# 1-Main.net
KiCad netlist of a schematic drawn in Altium Designer
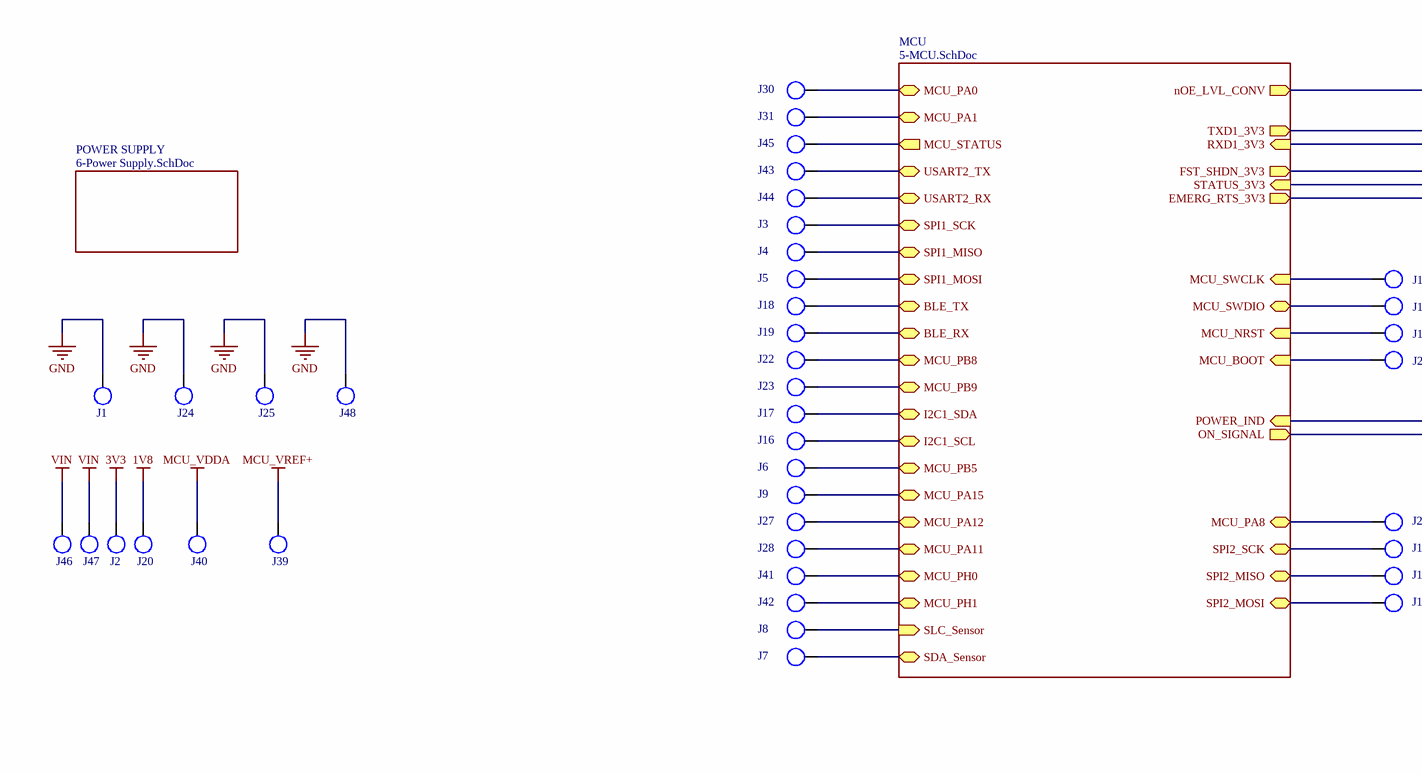
[diagram p0: 1-Main.SchDoc, left]
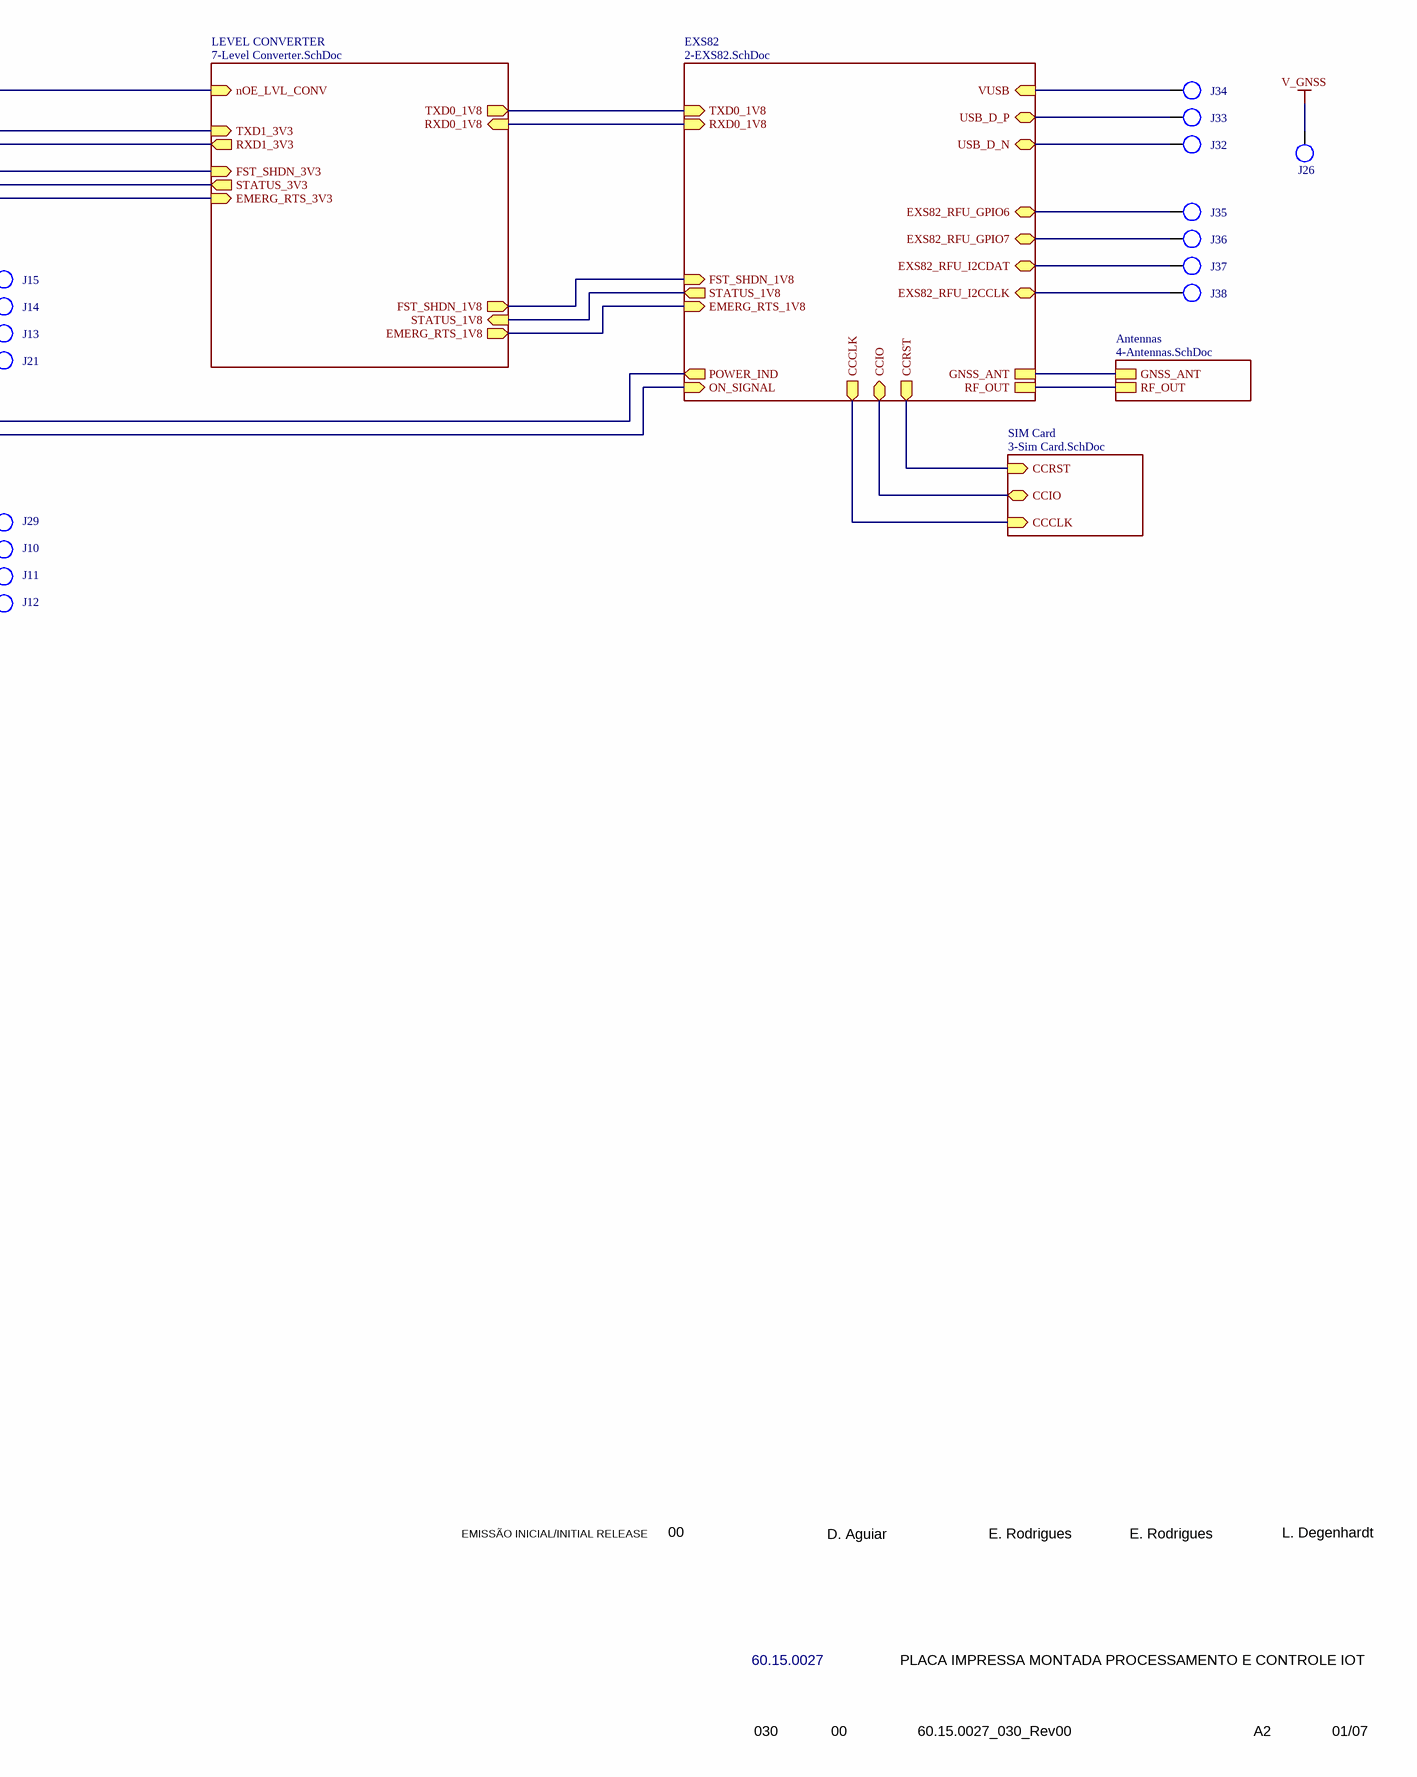
[diagram p1: 1-Main.SchDoc, right]

(export (version "E")
  (design (tool "Eeschema 10.0.6"))
  (components
    (comp (ref "J1")
      (value "CASTELATION")
      (footprint "CASTELATION")
      (libsource (lib "OMNI-SEM-COD") (part "CASTELATION"))
    )
    (comp (ref "J2")
      (value "CASTELATION")
      (footprint "CASTELATION")
      (libsource (lib "OMNI-SEM-COD") (part "CASTELATION"))
    )
    (comp (ref "J3")
      (value "CASTELATION")
      (footprint "CASTELATION")
      (libsource (lib "OMNI-SEM-COD") (part "CASTELATION"))
    )
    (comp (ref "J4")
      (value "CASTELATION")
      (footprint "CASTELATION")
      (libsource (lib "OMNI-SEM-COD") (part "CASTELATION"))
    )
    (comp (ref "J5")
      (value "CASTELATION")
      (footprint "CASTELATION")
      (libsource (lib "OMNI-SEM-COD") (part "CASTELATION"))
    )
    (comp (ref "J6")
      (value "CASTELATION")
      (footprint "CASTELATION")
      (libsource (lib "OMNI-SEM-COD") (part "CASTELATION"))
    )
    (comp (ref "J7")
      (value "CASTELATION")
      (footprint "CASTELATION")
      (libsource (lib "OMNI-SEM-COD") (part "CASTELATION"))
    )
    (comp (ref "J8")
      (value "CASTELATION")
      (footprint "CASTELATION")
      (libsource (lib "OMNI-SEM-COD") (part "CASTELATION"))
    )
    (comp (ref "J9")
      (value "CASTELATION")
      (footprint "CASTELATION")
      (libsource (lib "OMNI-SEM-COD") (part "CASTELATION"))
    )
    (comp (ref "J10")
      (value "CASTELATION")
      (footprint "CASTELATION")
      (libsource (lib "OMNI-SEM-COD") (part "CASTELATION"))
    )
    (comp (ref "J11")
      (value "CASTELATION")
      (footprint "CASTELATION")
      (libsource (lib "OMNI-SEM-COD") (part "CASTELATION"))
    )
    (comp (ref "J12")
      (value "CASTELATION")
      (footprint "CASTELATION")
      (libsource (lib "OMNI-SEM-COD") (part "CASTELATION"))
    )
    (comp (ref "J13")
      (value "CASTELATION")
      (footprint "CASTELATION")
      (libsource (lib "OMNI-SEM-COD") (part "CASTELATION"))
    )
    (comp (ref "J14")
      (value "CASTELATION")
      (footprint "CASTELATION")
      (libsource (lib "OMNI-SEM-COD") (part "CASTELATION"))
    )
    (comp (ref "J15")
      (value "CASTELATION")
      (footprint "CASTELATION")
      (libsource (lib "OMNI-SEM-COD") (part "CASTELATION"))
    )
    (comp (ref "J16")
      (value "CASTELATION")
      (footprint "CASTELATION")
      (libsource (lib "OMNI-SEM-COD") (part "CASTELATION"))
    )
    (comp (ref "J17")
      (value "CASTELATION")
      (footprint "CASTELATION")
      (libsource (lib "OMNI-SEM-COD") (part "CASTELATION"))
    )
    (comp (ref "J18")
      (value "CASTELATION")
      (footprint "CASTELATION")
      (libsource (lib "OMNI-SEM-COD") (part "CASTELATION"))
    )
    (comp (ref "J19")
      (value "CASTELATION")
      (footprint "CASTELATION")
      (libsource (lib "OMNI-SEM-COD") (part "CASTELATION"))
    )
    (comp (ref "J20")
      (value "CASTELATION")
      (footprint "CASTELATION")
      (libsource (lib "OMNI-SEM-COD") (part "CASTELATION"))
    )
    (comp (ref "J21")
      (value "CASTELATION")
      (footprint "CASTELATION")
      (libsource (lib "OMNI-SEM-COD") (part "CASTELATION"))
    )
    (comp (ref "J22")
      (value "CASTELATION")
      (footprint "CASTELATION")
      (libsource (lib "OMNI-SEM-COD") (part "CASTELATION"))
    )
    (comp (ref "J23")
      (value "CASTELATION")
      (footprint "CASTELATION")
      (libsource (lib "OMNI-SEM-COD") (part "CASTELATION"))
    )
    (comp (ref "J24")
      (value "CASTELATION")
      (footprint "CASTELATION")
      (libsource (lib "OMNI-SEM-COD") (part "CASTELATION"))
    )
    (comp (ref "J25")
      (value "CASTELATION")
      (footprint "CASTELATION")
      (libsource (lib "OMNI-SEM-COD") (part "CASTELATION"))
    )
    (comp (ref "J26")
      (value "CASTELATION")
      (footprint "CASTELATION")
      (libsource (lib "OMNI-SEM-COD") (part "CASTELATION"))
    )
    (comp (ref "J27")
      (value "CASTELATION")
      (footprint "CASTELATION")
      (libsource (lib "OMNI-SEM-COD") (part "CASTELATION"))
    )
    (comp (ref "J28")
      (value "CASTELATION")
      (footprint "CASTELATION")
      (libsource (lib "OMNI-SEM-COD") (part "CASTELATION"))
    )
    (comp (ref "J29")
      (value "CASTELATION")
      (footprint "CASTELATION")
      (libsource (lib "OMNI-SEM-COD") (part "CASTELATION"))
    )
    (comp (ref "J30")
      (value "CASTELATION")
      (footprint "CASTELATION")
      (libsource (lib "OMNI-SEM-COD") (part "CASTELATION"))
    )
    (comp (ref "J31")
      (value "CASTELATION")
      (footprint "CASTELATION")
      (libsource (lib "OMNI-SEM-COD") (part "CASTELATION"))
    )
    (comp (ref "J32")
      (value "CASTELATION")
      (footprint "CASTELATION")
      (libsource (lib "OMNI-SEM-COD") (part "CASTELATION"))
    )
    (comp (ref "J33")
      (value "CASTELATION")
      (footprint "CASTELATION")
      (libsource (lib "OMNI-SEM-COD") (part "CASTELATION"))
    )
    (comp (ref "J34")
      (value "CASTELATION")
      (footprint "CASTELATION")
      (libsource (lib "OMNI-SEM-COD") (part "CASTELATION"))
    )
    (comp (ref "J35")
      (value "CASTELATION")
      (footprint "CASTELATION")
      (libsource (lib "OMNI-SEM-COD") (part "CASTELATION"))
    )
    (comp (ref "J36")
      (value "CASTELATION")
      (footprint "CASTELATION")
      (libsource (lib "OMNI-SEM-COD") (part "CASTELATION"))
    )
    (comp (ref "J37")
      (value "CASTELATION")
      (footprint "CASTELATION")
      (libsource (lib "OMNI-SEM-COD") (part "CASTELATION"))
    )
    (comp (ref "J38")
      (value "CASTELATION")
      (footprint "CASTELATION")
      (libsource (lib "OMNI-SEM-COD") (part "CASTELATION"))
    )
    (comp (ref "J39")
      (value "CASTELATION")
      (footprint "CASTELATION")
      (libsource (lib "OMNI-SEM-COD") (part "CASTELATION"))
    )
    (comp (ref "J40")
      (value "CASTELATION")
      (footprint "CASTELATION")
      (libsource (lib "OMNI-SEM-COD") (part "CASTELATION"))
    )
    (comp (ref "J41")
      (value "CASTELATION")
      (footprint "CASTELATION")
      (libsource (lib "OMNI-SEM-COD") (part "CASTELATION"))
    )
    (comp (ref "J42")
      (value "CASTELATION")
      (footprint "CASTELATION")
      (libsource (lib "OMNI-SEM-COD") (part "CASTELATION"))
    )
    (comp (ref "J43")
      (value "CASTELATION")
      (footprint "CASTELATION")
      (libsource (lib "OMNI-SEM-COD") (part "CASTELATION"))
    )
    (comp (ref "J44")
      (value "CASTELATION")
      (footprint "CASTELATION")
      (libsource (lib "OMNI-SEM-COD") (part "CASTELATION"))
    )
    (comp (ref "J45")
      (value "CASTELATION")
      (footprint "CASTELATION")
      (libsource (lib "OMNI-SEM-COD") (part "CASTELATION"))
    )
    (comp (ref "J46")
      (value "CASTELATION")
      (footprint "CASTELATION")
      (libsource (lib "OMNI-SEM-COD") (part "CASTELATION"))
    )
    (comp (ref "J47")
      (value "CASTELATION")
      (footprint "CASTELATION")
      (libsource (lib "OMNI-SEM-COD") (part "CASTELATION"))
    )
    (comp (ref "J48")
      (value "CASTELATION")
      (footprint "CASTELATION")
      (libsource (lib "OMNI-SEM-COD") (part "CASTELATION"))
    )
  )
  (nets
    (net (code "1") (name "/BLE_RX") (class "Default")
      (node (ref "J19") (pin "1") (pinfunction "1_1") (pintype "passive"))
    )
    (net (code "2") (name "/BLE_TX") (class "Default")
      (node (ref "J18") (pin "1") (pinfunction "1_1") (pintype "passive"))
    )
    (net (code "8") (name "/EXS82_RFU_GPIO6") (class "Default")
      (node (ref "J35") (pin "1") (pinfunction "1_1") (pintype "passive"))
    )
    (net (code "9") (name "/EXS82_RFU_GPIO7") (class "Default")
      (node (ref "J36") (pin "1") (pinfunction "1_1") (pintype "passive"))
    )
    (net (code "10") (name "/EXS82_RFU_I2CCLK") (class "Default")
      (node (ref "J38") (pin "1") (pinfunction "1_1") (pintype "passive"))
    )
    (net (code "11") (name "/EXS82_RFU_I2CDAT") (class "Default")
      (node (ref "J37") (pin "1") (pinfunction "1_1") (pintype "passive"))
    )
    (net (code "15") (name "/I2C1_SCL") (class "Default")
      (node (ref "J16") (pin "1") (pinfunction "1_1") (pintype "passive"))
    )
    (net (code "16") (name "/I2C1_SDA") (class "Default")
      (node (ref "J17") (pin "1") (pinfunction "1_1") (pintype "passive"))
    )
    (net (code "17") (name "/MCU_BOOT") (class "Default")
      (node (ref "J21") (pin "1") (pinfunction "1_1") (pintype "passive"))
    )
    (net (code "18") (name "/MCU_NRST") (class "Default")
      (node (ref "J13") (pin "1") (pinfunction "1_1") (pintype "passive"))
    )
    (net (code "19") (name "/MCU_PA0") (class "Default")
      (node (ref "J30") (pin "1") (pinfunction "1_1") (pintype "passive"))
    )
    (net (code "20") (name "/MCU_PA1") (class "Default")
      (node (ref "J31") (pin "1") (pinfunction "1_1") (pintype "passive"))
    )
    (net (code "21") (name "/MCU_PA8") (class "Default")
      (node (ref "J29") (pin "1") (pinfunction "1_1") (pintype "passive"))
    )
    (net (code "22") (name "/MCU_PA11") (class "Default")
      (node (ref "J28") (pin "1") (pinfunction "1_1") (pintype "passive"))
    )
    (net (code "23") (name "/MCU_PA12") (class "Default")
      (node (ref "J27") (pin "1") (pinfunction "1_1") (pintype "passive"))
    )
    (net (code "24") (name "/MCU_PA15") (class "Default")
      (node (ref "J9") (pin "1") (pinfunction "1_1") (pintype "passive"))
    )
    (net (code "25") (name "/MCU_PB5") (class "Default")
      (node (ref "J6") (pin "1") (pinfunction "1_1") (pintype "passive"))
    )
    (net (code "26") (name "/MCU_PB8") (class "Default")
      (node (ref "J22") (pin "1") (pinfunction "1_1") (pintype "passive"))
    )
    (net (code "27") (name "/MCU_PB9") (class "Default")
      (node (ref "J23") (pin "1") (pinfunction "1_1") (pintype "passive"))
    )
    (net (code "28") (name "/MCU_PH0") (class "Default")
      (node (ref "J41") (pin "1") (pinfunction "1_1") (pintype "passive"))
    )
    (net (code "29") (name "/MCU_PH1") (class "Default")
      (node (ref "J42") (pin "1") (pinfunction "1_1") (pintype "passive"))
    )
    (net (code "30") (name "/MCU_STATUS") (class "Default")
      (node (ref "J45") (pin "1") (pinfunction "1_1") (pintype "passive"))
    )
    (net (code "31") (name "/MCU_SWCLK") (class "Default")
      (node (ref "J15") (pin "1") (pinfunction "1_1") (pintype "passive"))
    )
    (net (code "32") (name "/MCU_SWDIO") (class "Default")
      (node (ref "J14") (pin "1") (pinfunction "1_1") (pintype "passive"))
    )
    (net (code "38") (name "/SDA_Sensor") (class "Default")
      (node (ref "J7") (pin "1") (pinfunction "1_1") (pintype "passive"))
    )
    (net (code "39") (name "/SLC_Sensor") (class "Default")
      (node (ref "J8") (pin "1") (pinfunction "1_1") (pintype "passive"))
    )
    (net (code "40") (name "/SPI1_MISO") (class "Default")
      (node (ref "J4") (pin "1") (pinfunction "1_1") (pintype "passive"))
    )
    (net (code "41") (name "/SPI1_MOSI") (class "Default")
      (node (ref "J5") (pin "1") (pinfunction "1_1") (pintype "passive"))
    )
    (net (code "42") (name "/SPI1_SCK") (class "Default")
      (node (ref "J3") (pin "1") (pinfunction "1_1") (pintype "passive"))
    )
    (net (code "43") (name "/SPI2_MISO") (class "Default")
      (node (ref "J11") (pin "1") (pinfunction "1_1") (pintype "passive"))
    )
    (net (code "44") (name "/SPI2_MOSI") (class "Default")
      (node (ref "J12") (pin "1") (pinfunction "1_1") (pintype "passive"))
    )
    (net (code "45") (name "/SPI2_SCK") (class "Default")
      (node (ref "J10") (pin "1") (pinfunction "1_1") (pintype "passive"))
    )
    (net (code "50") (name "/USART2_RX") (class "Default")
      (node (ref "J44") (pin "1") (pinfunction "1_1") (pintype "passive"))
    )
    (net (code "51") (name "/USART2_TX") (class "Default")
      (node (ref "J43") (pin "1") (pinfunction "1_1") (pintype "passive"))
    )
    (net (code "52") (name "/USB_D_N") (class "Default")
      (node (ref "J32") (pin "1") (pinfunction "1_1") (pintype "passive"))
    )
    (net (code "53") (name "/USB_D_P") (class "Default")
      (node (ref "J33") (pin "1") (pinfunction "1_1") (pintype "passive"))
    )
    (net (code "54") (name "/VUSB") (class "Default")
      (node (ref "J34") (pin "1") (pinfunction "1_1") (pintype "passive"))
    )
    (net (code "56") (name "1V8") (class "Default")
      (node (ref "J20") (pin "1") (pinfunction "1_1") (pintype "passive"))
    )
    (net (code "57") (name "3V3") (class "Default")
      (node (ref "J2") (pin "1") (pinfunction "1_1") (pintype "passive"))
    )
    (net (code "58") (name "GND") (class "Default")
      (node (ref "J1") (pin "1") (pinfunction "1_1") (pintype "passive"))
      (node (ref "J24") (pin "1") (pinfunction "1_1") (pintype "passive"))
      (node (ref "J25") (pin "1") (pinfunction "1_1") (pintype "passive"))
      (node (ref "J48") (pin "1") (pinfunction "1_1") (pintype "passive"))
    )
    (net (code "59") (name "MCU_VDDA") (class "Default")
      (node (ref "J40") (pin "1") (pinfunction "1_1") (pintype "passive"))
    )
    (net (code "60") (name "MCU_VREF+") (class "Default")
      (node (ref "J39") (pin "1") (pinfunction "1_1") (pintype "passive"))
    )
    (net (code "61") (name "VIN") (class "Default")
      (node (ref "J46") (pin "1") (pinfunction "1_1") (pintype "passive"))
      (node (ref "J47") (pin "1") (pinfunction "1_1") (pintype "passive"))
    )
    (net (code "62") (name "V_GNSS") (class "Default")
      (node (ref "J26") (pin "1") (pinfunction "1_1") (pintype "passive"))
    )
  )
)
